# 24V_Buck_3_3V.net
KiCad netlist of a schematic drawn in Altium Designer
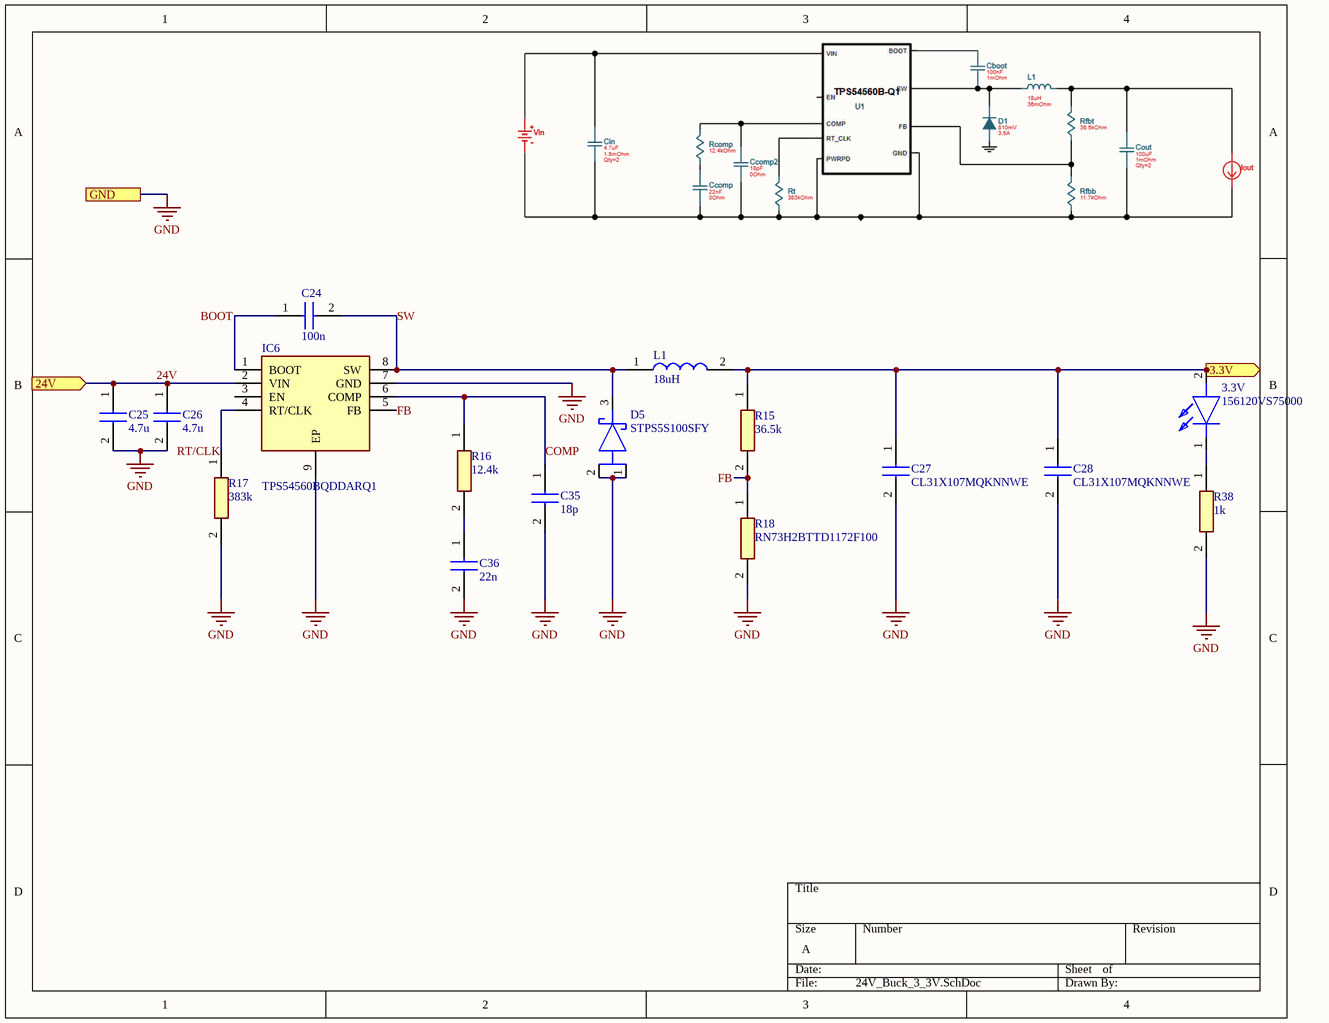
[diagram p0: 24V_Buck_3_3V.SchDoc]

(export (version "E")
  (design (tool "Eeschema 10.0.6"))
  (components
    (comp (ref "3.3V")
      (value "156120VS75000")
      (footprint "SamacSys:156120VS75000")
      (description "LED")
      (fields (field (name "MOUSER PART NUMBER") "710-156120VS75000"))
      (libsource (lib "SamacSys") (part "156120VS75000"))
    )
    (comp (ref "C24")
      (value "100n")
      (footprint "SamacSys:CAPC3216X94N")
      (description "Capacitor")
      (fields
        (field (name "MANUFACTURER_PART_NUMBER") "12065C104J4Z2A")
        (field (name "MOUSER PART NUMBER") "581-12065C104J4Z2A")
      )
      (libsource (lib "SamacSys") (part "12065C104J4Z2A"))
    )
    (comp (ref "C25")
      (value "4.7u")
      (footprint "SamacSys:CAPC3216X180N")
      (description "Capacitor")
      (fields
        (field (name "MANUFACTURER_PART_NUMBER") "GMK316AB7475KLHT")
        (field (name "MOUSER PART NUMBER") "963-GMK316AB7475KLHT")
      )
      (libsource (lib "SamacSys") (part "GMK316AB7475KLHT"))
    )
    (comp (ref "C26")
      (value "4.7u")
      (footprint "SamacSys:CAPC3216X180N")
      (description "Capacitor")
      (fields
        (field (name "MANUFACTURER_PART_NUMBER") "GMK316AB7475KLHT")
        (field (name "MOUSER PART NUMBER") "963-GMK316AB7475KLHT")
      )
      (libsource (lib "SamacSys") (part "GMK316AB7475KLHT"))
    )
    (comp (ref "C27")
      (value "CL31X107MQKNNWE")
      (footprint "SamacSys:CAPC3216X190N")
      (description "Capacitor")
      (fields (field (name "MOUSER PART NUMBER") "187-CL31X107MQKNNWE"))
      (libsource (lib "*") (part "CL31X107MQKNNWE"))
    )
    (comp (ref "C28")
      (value "CL31X107MQKNNWE")
      (footprint "SamacSys:CAPC3216X190N")
      (description "Capacitor")
      (fields (field (name "MOUSER PART NUMBER") "187-CL31X107MQKNNWE"))
      (libsource (lib "*") (part "CL31X107MQKNNWE"))
    )
    (comp (ref "C35")
      (value "18p")
      (footprint "SamacSys:C1206")
      (description "Capacitor")
      (fields (field (name "MANUFACTURER_PART_NUMBER") "C1206C180FGGACTU"))
      (libsource (lib "*") (part "C1206C180FGGACTU"))
    )
    (comp (ref "C36")
      (value "22n")
      (footprint "SamacSys:CAPC3216X170N")
      (description "Capacitor")
      (fields
        (field (name "MANUFACTURER_PART_NUMBER") "VJ1206Y223KXBAC")
        (field (name "MOUSER PART NUMBER") "77-VJ1206Y223KXBAC")
      )
      (libsource (lib "*") (part "VJ1206Y223KXBAC"))
    )
    (comp (ref "D5")
      (value "STPS5S100SFY")
      (footprint "SamacSys:STPS10L40CSF")
      (description "Schottky Diode with Dual Anode")
      (fields (field (name "MOUSER PART NUMBER") "511-STPS5S100SFY"))
      (libsource (lib "*") (part "STPS5S100SFY"))
    )
    (comp (ref "IC6")
      (value "TPS54560BQDDARQ1")
      (footprint "SamacSys:SOIC127P600X170-9N")
      (description "Integrated Circuit")
      (fields (field (name "MOUSER PART NUMBER") "595-TPS54560BQDDARQ1"))
      (libsource (lib "*") (part "TPS54560BQDDARQ1"))
    )
    (comp (ref "L1")
      (value "18uH")
      (footprint "SamacSys:INDPM125125X800N")
      (description "Inductor")
      (fields
        (field (name "MANUFACTURER_PART_NUMBER") "SRR1280-180M")
        (field (name "MOUSER PART NUMBER") "652-SRR1280-180M")
      )
      (libsource (lib "*") (part "SRR1280-180M"))
    )
    (comp (ref "R15")
      (value "36.5k")
      (footprint "SamacSys:RESC3116X65N")
      (description "Resistor")
      (fields
        (field (name "MANUFACTURER_PART_NUMBER") "CRCW120636K5FKEAHP")
        (field (name "MOUSER PART NUMBER") "71-CRCW120636K5FKEAH")
      )
      (libsource (lib "*") (part "CRCW120636K5FKEAHP"))
    )
    (comp (ref "R16")
      (value "12.4k")
      (footprint "SamacSys:ERJUP6")
      (description "Resistor")
      (fields
        (field (name "MANUFACTURER_PART_NUMBER") "ERJ-UP6F1242V")
        (field (name "MOUSER PART NUMBER") "667-ERJ-UP6F1242V")
      )
      (libsource (lib "*") (part "ERJ-UP6F1242V"))
    )
    (comp (ref "R17")
      (value "383k")
      (footprint "SamacSys:RESC3216X70N")
      (description "Resistor")
      (fields (field (name "MANUFACTURER_PART_NUMBER") "ERA-8AEB3833V"))
      (libsource (lib "*") (part "ERA-8AEB3833V"))
    )
    (comp (ref "R18")
      (value "RN73H2BTTD1172F100")
      (footprint "SamacSys:RESC3216X70N")
      (description "Resistor")
      (fields (field (name "MOUSER PART NUMBER") "660-RN73H2BT1172F100"))
      (libsource (lib "*") (part "RN73H2BTTD1172F100"))
    )
    (comp (ref "R38")
      (value "1k")
      (footprint "SamacSys:RESC3116X65N")
      (description "Resistor")
      (fields
        (field (name "MANUFACTURER_PART_NUMBER") "CRGS1206J1K0")
        (field (name "MOUSER PART NUMBER") "279-CRGS1206J1K0")
      )
      (libsource (lib "*") (part "CRGS1206J1K0"))
    )
  )
  (nets
    (net (code "1") (name "/3.3V") (class "Default")
      (node (ref "3.3V") (pin "2") (pinfunction "A_2") (pintype "passive"))
      (node (ref "C27") (pin "1") (pinfunction "1_1") (pintype "passive"))
      (node (ref "C28") (pin "1") (pinfunction "1_1") (pintype "passive"))
      (node (ref "L1") (pin "2") (pinfunction "2_2") (pintype "passive"))
      (node (ref "R15") (pin "1") (pinfunction "1_1") (pintype "passive"))
    )
    (net (code "2") (name "/24V") (class "Default")
      (node (ref "C25") (pin "1") (pinfunction "1_1") (pintype "passive"))
      (node (ref "C26") (pin "1") (pinfunction "1_1") (pintype "passive"))
      (node (ref "IC6") (pin "2") (pinfunction "VIN_2") (pintype "passive"))
    )
    (net (code "3") (name "/BOOT") (class "Default")
      (node (ref "C24") (pin "1") (pinfunction "1_1") (pintype "passive"))
      (node (ref "IC6") (pin "1") (pinfunction "BOOT_1") (pintype "passive"))
    )
    (net (code "4") (name "/COMP") (class "Default")
      (node (ref "C35") (pin "1") (pinfunction "1_1") (pintype "passive"))
      (node (ref "IC6") (pin "6") (pinfunction "COMP_6") (pintype "passive"))
      (node (ref "R16") (pin "1") (pinfunction "1_1") (pintype "passive"))
    )
    (net (code "5") (name "/FB") (class "Default")
      (node (ref "IC6") (pin "5") (pinfunction "FB_5") (pintype "passive"))
      (node (ref "R15") (pin "2") (pinfunction "2_2") (pintype "passive"))
      (node (ref "R18") (pin "1") (pinfunction "1_1") (pintype "passive"))
    )
    (net (code "6") (name "/RT{slash}CLK") (class "Default")
      (node (ref "IC6") (pin "4") (pinfunction "RT/CLK_4") (pintype "passive"))
      (node (ref "R17") (pin "1") (pinfunction "1_1") (pintype "passive"))
    )
    (net (code "7") (name "/SW") (class "Default")
      (node (ref "C24") (pin "2") (pinfunction "2_2") (pintype "passive"))
      (node (ref "D5") (pin "3") (pinfunction "K_3") (pintype "passive"))
      (node (ref "IC6") (pin "8") (pinfunction "SW_8") (pintype "passive"))
      (node (ref "L1") (pin "1") (pinfunction "1_1") (pintype "passive"))
    )
    (net (code "8") (name "GND") (class "Default")
      (node (ref "C25") (pin "2") (pinfunction "2_2") (pintype "passive"))
      (node (ref "C26") (pin "2") (pinfunction "2_2") (pintype "passive"))
      (node (ref "C27") (pin "2") (pinfunction "2_2") (pintype "passive"))
      (node (ref "C28") (pin "2") (pinfunction "2_2") (pintype "passive"))
      (node (ref "C35") (pin "2") (pinfunction "2_2") (pintype "passive"))
      (node (ref "C36") (pin "2") (pinfunction "2_2") (pintype "passive"))
      (node (ref "D5") (pin "1") (pinfunction "A1_1") (pintype "passive"))
      (node (ref "D5") (pin "2") (pinfunction "A2_2") (pintype "passive"))
      (node (ref "IC6") (pin "7") (pinfunction "GND_7") (pintype "passive"))
      (node (ref "IC6") (pin "9") (pinfunction "EP_9") (pintype "passive"))
      (node (ref "R17") (pin "2") (pinfunction "2_2") (pintype "passive"))
      (node (ref "R18") (pin "2") (pinfunction "2_2") (pintype "passive"))
      (node (ref "R38") (pin "2") (pinfunction "2_2") (pintype "passive"))
    )
    (net (code "9") (name "Net-(3.3V-K)") (class "Default")
      (node (ref "3.3V") (pin "1") (pinfunction "K_1") (pintype "passive"))
      (node (ref "R38") (pin "1") (pinfunction "1_1") (pintype "passive"))
    )
    (net (code "10") (name "Net-(C36-Pad1)") (class "Default")
      (node (ref "C36") (pin "1") (pinfunction "1_1") (pintype "passive"))
      (node (ref "R16") (pin "2") (pinfunction "2_2") (pintype "passive"))
    )
    (net (code "11") (name "unconnected-(IC6-EN-Pad3)") (class "Default")
      (node (ref "IC6") (pin "3") (pinfunction "EN_3") (pintype "passive"))
    )
  )
)
